# CM_DM_Filter.net
KiCad netlist of a schematic drawn in Altium Designer
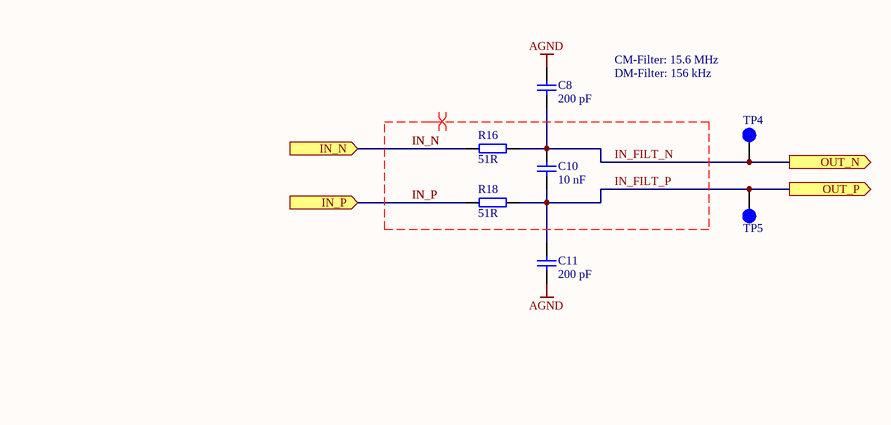
[diagram p0: CM_DM_Filter.SchDoc]

(export (version "E")
  (design (tool "Eeschema 10.0.6"))
  (components
    (comp (ref "C8")
      (value "200 pF")
      (footprint "C_0402_TE")
      (description "Generic capacitor")
      (fields
        (field (name "MANUFACTURER PART NUMBER") "UZgen_C_0402_200pF_50V_NP0")
        (field (name "MANUFACTURER") "UZgen")
        (field (name "CREATED FROM") "UZgenTool")
      )
      (libsource (lib "user") (part "CAP-NP"))
    )
    (comp (ref "C10")
      (value "10 nF")
      (footprint "C_0402_TE")
      (description "Generic capacitor")
      (fields
        (field (name "MANUFACTURER PART NUMBER") "UZgen_C_0402_10nF_50V_NP0")
        (field (name "MANUFACTURER") "UZgen")
        (field (name "CREATED FROM") "UZgenTool")
      )
      (libsource (lib "user") (part "CAP-NP"))
    )
    (comp (ref "C11")
      (value "200 pF")
      (footprint "C_0402_TE")
      (description "Generic capacitor")
      (fields
        (field (name "MANUFACTURER PART NUMBER") "UZgen_C_0402_200pF_50V_NP0")
        (field (name "MANUFACTURER") "UZgen")
        (field (name "CREATED FROM") "UZgenTool")
      )
      (libsource (lib "user") (part "CAP-NP"))
    )
    (comp (ref "R16")
      (value "51R")
      (footprint "R_0402_TE")
      (description "Generic resistor")
      (fields
        (field (name "MANUFACTURER PART NUMBER") "UZgen_R_0402_51R")
        (field (name "MANUFACTURER") "UZgen")
        (field (name "CREATED FROM") "UZgenTool")
      )
      (libsource (lib "user") (part "RES"))
    )
    (comp (ref "R18")
      (value "51R")
      (footprint "R_0402_TE")
      (description "Generic resistor")
      (fields
        (field (name "MANUFACTURER PART NUMBER") "UZgen_R_0402_51R")
        (field (name "MANUFACTURER") "UZgen")
        (field (name "CREATED FROM") "UZgenTool")
      )
      (libsource (lib "user") (part "RES"))
    )
    (comp (ref "TP4")
      (value "Testpoint 1mm")
      (footprint "TP_1mm")
      (fields
        (field (name "MANUFACTURER PART NUMBER") "Testpoint_1mm")
        (field (name "MANUFACTURER") "UltraZohm")
        (field (name "CREATED") "2018_06_25_AGeiger")
        (field (name "CREATED FROM") "AGeiger")
      )
      (libsource (lib "user") (part "TP_1mm"))
    )
    (comp (ref "TP5")
      (value "Testpoint 1mm")
      (footprint "TP_1mm")
      (fields
        (field (name "MANUFACTURER PART NUMBER") "Testpoint_1mm")
        (field (name "MANUFACTURER") "UltraZohm")
        (field (name "CREATED") "2018_06_25_AGeiger")
        (field (name "CREATED FROM") "AGeiger")
      )
      (libsource (lib "user") (part "TP_1mm"))
    )
  )
  (nets
    (net (code "1") (name "/IN_FILT_N") (class "Default")
      (node (ref "C10") (pin "1") (pinfunction "1_1") (pintype "passive"))
      (node (ref "C8") (pin "2") (pinfunction "2_2") (pintype "passive"))
      (node (ref "R16") (pin "2") (pinfunction "2_2") (pintype "passive"))
      (node (ref "TP4") (pin "1") (pintype "passive"))
    )
    (net (code "2") (name "/IN_FILT_P") (class "Default")
      (node (ref "C10") (pin "2") (pinfunction "2_2") (pintype "passive"))
      (node (ref "C11") (pin "1") (pinfunction "1_1") (pintype "passive"))
      (node (ref "R18") (pin "2") (pinfunction "2_2") (pintype "passive"))
      (node (ref "TP5") (pin "1") (pintype "passive"))
    )
    (net (code "3") (name "/IN_N") (class "Default")
      (node (ref "R16") (pin "1") (pinfunction "1_1") (pintype "passive"))
    )
    (net (code "4") (name "/IN_P") (class "Default")
      (node (ref "R18") (pin "1") (pinfunction "1_1") (pintype "passive"))
    )
    (net (code "5") (name "AGND") (class "Default")
      (node (ref "C11") (pin "2") (pinfunction "2_2") (pintype "passive"))
      (node (ref "C8") (pin "1") (pinfunction "1_1") (pintype "passive"))
    )
  )
)
